# Power.net
KiCad netlist of a schematic drawn in Altium Designer
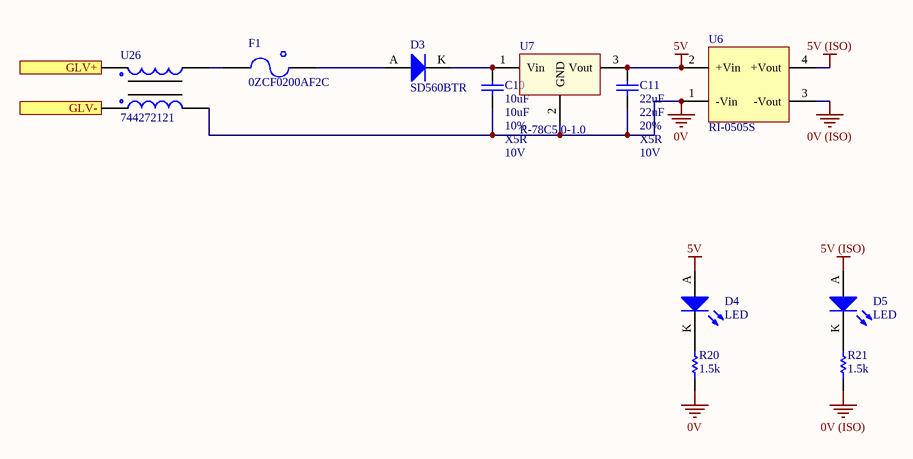
[diagram p0: Power.SchDoc]

(export (version "E")
  (design (tool "Eeschema 10.0.6"))
  (components
    (comp (ref "C10")
      (value "10uF")
      (footprint "0805")
      (fields
        (field (name "ALTIUM_VALUE") "10uF")
        (field (name "TOLERANCE") "10%")
        (field (name "MATERIAL") "X5R")
        (field (name "RATED VOLTAGE") "10V")
        (field (name "MANUFACTURER") "muRata")
        (field (name "PART NUMBER") "GCM21BR61A106KA37L")
      )
      (libsource (lib "ts_19-standard-library") (part "Capacitor"))
    )
    (comp (ref "C11")
      (value "22uF")
      (footprint "0805")
      (fields
        (field (name "ALTIUM_VALUE") "22uF")
        (field (name "TOLERANCE") "20%")
        (field (name "MATERIAL") "X5R")
        (field (name "RATED VOLTAGE") "10V")
        (field (name "MANUFACTURER") "muRata")
        (field (name "DIGIKEY PART NUMBER") "490-10511-1-ND")
        (field (name "PART NUMBER") "GRM21BR61A226ME51L")
      )
      (libsource (lib "ts_19-standard-library") (part "Capacitor"))
    )
    (comp (ref "D3")
      (value "SD560BTR")
      (footprint "SMB Diode")
      (description "1.2V_F 600V 5A SMB")
      (fields
        (field (name "MANUFACTURER") "SMC Diode Solutions")
        (field (name "DIGIKEY PART NUMBER") "1655-1530-2-ND")
      )
      (libsource (lib "ts_19-standard-library") (part "Diode"))
    )
    (comp (ref "D4")
      (value "LED")
      (footprint "0805 LED")
      (description "Red LED Indication - Discrete 1.75V 0805 (2012 Metric)")
      (fields (field (name "MANUFACTURER") "ROHM Semiconductor") (field (name "PART NUMBER") "SML-210LTT86"))
      (libsource (lib "ts_19-standard-library") (part "LED"))
    )
    (comp (ref "D5")
      (value "LED")
      (footprint "0805 LED")
      (description "Red LED Indication - Discrete 1.75V 0805 (2012 Metric)")
      (fields (field (name "MANUFACTURER") "ROHM Semiconductor") (field (name "PART NUMBER") "SML-210LTT86"))
      (libsource (lib "ts_19-standard-library") (part "LED"))
    )
    (comp (ref "F1")
      (value "0ZCF0200AF2C")
      (footprint "2920")
      (description "SMD 24V 2A Fuse")
      (fields
        (field (name "MANUFACTURER") "Bel Fuse Inc")
        (field (name "DIGIKEY PART NUMBER") "507-1749-2-ND")
      )
      (libsource (lib "ts_19-standard-library") (part "PTC Fuse"))
    )
    (comp (ref "R20")
      (value "1.5k")
      (footprint "0805")
      (fields
        (field (name "MANUFACTURER") "YAGEO")
        (field (name "PART NUMBER") "RC0805FR071K5L")
        (field (name "TOLERANCE") "0.01")
      )
      (libsource (lib "ts_19-standard-library") (part "Resistor"))
    )
    (comp (ref "R21")
      (value "1.5k")
      (footprint "0805")
      (fields
        (field (name "MANUFACTURER") "YAGEO")
        (field (name "PART NUMBER") "RC0805FR071K5L")
        (field (name "TOLERANCE") "0.01")
      )
      (libsource (lib "ts_19-standard-library") (part "Resistor"))
    )
    (comp (ref "U6")
      (value "RI-0505S")
      (footprint "RECOM 4-SIP")
      (description "5V DC-DC Converter (2W)")
      (fields (field (name "MANUFACTURER") "Recom") (field (name "DIGIKEY PART NUMBER") "945-1189-ND"))
      (libsource (lib "ts_19-standard-library") (part "RI-0505S"))
    )
    (comp (ref "U7")
      (value "R-78C5.0-1.0")
      (footprint "RECOM 3-SIP")
      (description "CONV DC/DC 1A 5V OUT SIP VERT")
      (fields (field (name "MANUFACTURER") "Recom") (field (name "DIGIKEY PART NUMBER") "945-1395-5-ND"))
      (libsource (lib "ts_19-standard-library") (part "R-78C5.0-1.0"))
    )
    (comp (ref "U26")
      (value "744272121")
      (footprint "Wurth 4-PC Pad")
      (description "Common Mode Choke 120UH 2.5A 2LN 460 OHM SMD")
      (fields
        (field (name "MANUFACTURER") "Wurth Electronics Inc")
        (field (name "DIGIKEY PART NUMBER") "732-1489-2-ND")
      )
      (libsource (lib "ts_19-standard-library") (part "744272121"))
    )
  )
  (nets
    (net (code "1") (name "/GLV+") (class "Default")
      (node (ref "U26") (pin "1") (pinfunction "1_1") (pintype "passive"))
    )
    (net (code "2") (name "/GLV-") (class "Default")
      (node (ref "U26") (pin "4") (pinfunction "4_4") (pintype "passive"))
    )
    (net (code "3") (name "0V") (class "Default")
      (node (ref "C10") (pin "1") (pinfunction "1_1") (pintype "passive"))
      (node (ref "C11") (pin "1") (pinfunction "1_1") (pintype "passive"))
      (node (ref "R20") (pin "1") (pinfunction "1_1") (pintype "passive"))
      (node (ref "U26") (pin "3") (pinfunction "3_3") (pintype "power_in"))
      (node (ref "U6") (pin "1") (pinfunction "-Vin_1") (pintype "power_in"))
      (node (ref "U7") (pin "2") (pinfunction "GND_2") (pintype "passive"))
    )
    (net (code "4") (name "0V (ISO)") (class "Default")
      (node (ref "R21") (pin "1") (pinfunction "1_1") (pintype "passive"))
      (node (ref "U6") (pin "3") (pinfunction "-Vout_3") (pintype "power_in"))
    )
    (net (code "5") (name "5V") (class "Default")
      (node (ref "C11") (pin "2") (pinfunction "2_2") (pintype "passive"))
      (node (ref "D4") (pin "A") (pinfunction "A_A") (pintype "passive"))
      (node (ref "U6") (pin "2") (pinfunction "+Vin_2") (pintype "power_in"))
      (node (ref "U7") (pin "3") (pinfunction "Vout_3") (pintype "passive"))
    )
    (net (code "6") (name "5V (ISO)") (class "Default")
      (node (ref "D5") (pin "A") (pinfunction "A_A") (pintype "passive"))
      (node (ref "U6") (pin "4") (pinfunction "+Vout_4") (pintype "power_in"))
    )
    (net (code "7") (name "Net-(D3-PadA)") (class "Default")
      (node (ref "D3") (pin "A") (pinfunction "A_A") (pintype "passive"))
      (node (ref "F1") (pin "2") (pinfunction "2_2") (pintype "passive"))
    )
    (net (code "8") (name "Net-(D4-PadK)") (class "Default")
      (node (ref "D4") (pin "K") (pinfunction "K_K") (pintype "passive"))
      (node (ref "R20") (pin "2") (pinfunction "2_2") (pintype "passive"))
    )
    (net (code "9") (name "Net-(D5-PadK)") (class "Default")
      (node (ref "D5") (pin "K") (pinfunction "K_K") (pintype "passive"))
      (node (ref "R21") (pin "2") (pinfunction "2_2") (pintype "passive"))
    )
    (net (code "10") (name "Net-(F1-Pad1)") (class "Default")
      (node (ref "F1") (pin "1") (pinfunction "1_1") (pintype "passive"))
      (node (ref "U26") (pin "2") (pinfunction "2_2") (pintype "passive"))
    )
    (net (code "11") (name "Net-(U7-Vin)") (class "Default")
      (node (ref "C10") (pin "2") (pinfunction "2_2") (pintype "passive"))
      (node (ref "D3") (pin "K") (pinfunction "K_K") (pintype "passive"))
      (node (ref "U7") (pin "1") (pinfunction "Vin_1") (pintype "passive"))
    )
  )
)
